# Sheet1.net
KiCad netlist of a schematic drawn in Altium Designer
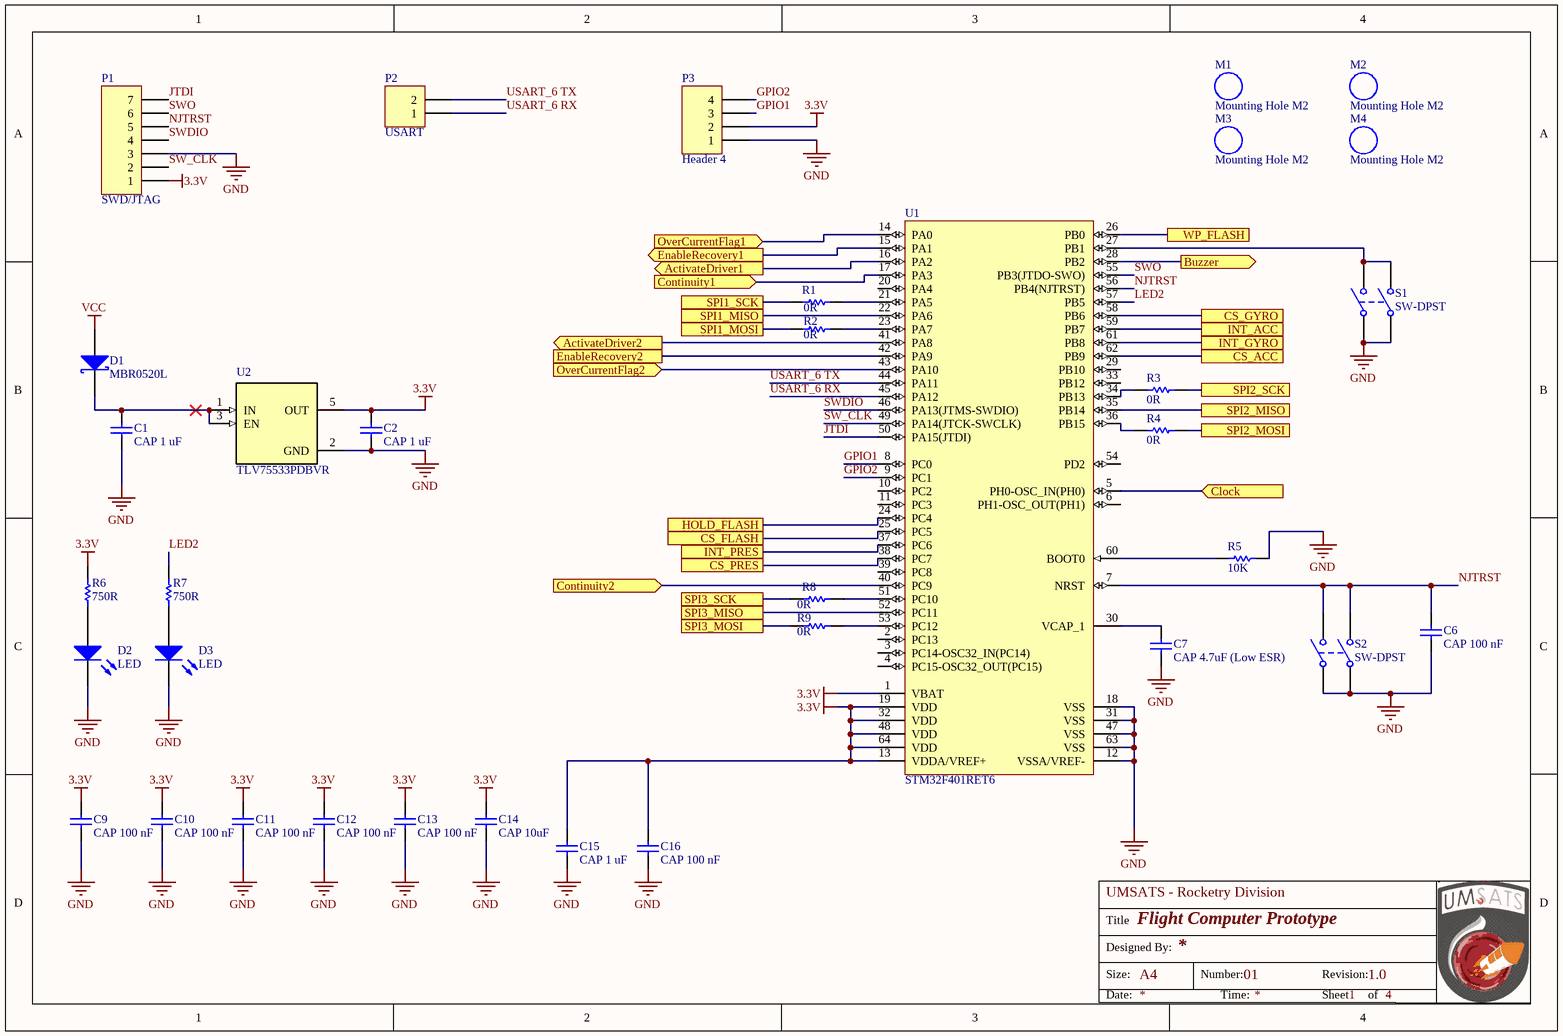
[diagram p0: Sheet1.SchDoc]

(export (version "E")
  (design (tool "Eeschema 10.0.6"))
  (components
    (comp (ref "C1")
      (value "CAP 1 uF")
      (footprint "CL10A105KB8NNNC")
      (description "Capacitor")
      (fields (field (name "PUBLISHER") "Altium Limited"))
      (libsource (lib "Miscellaneous Devices") (part "Cap"))
    )
    (comp (ref "C2")
      (value "CAP 1 uF")
      (footprint "CL10A105KB8NNNC")
      (description "Capacitor")
      (fields (field (name "PUBLISHER") "Altium Limited"))
      (libsource (lib "Miscellaneous Devices") (part "Cap"))
    )
    (comp (ref "C6")
      (value "CAP 100 nF")
      (footprint "06035C104KAT4A")
      (description "Capacitor")
      (fields (field (name "PUBLISHER") "Altium Limited"))
      (libsource (lib "Miscellaneous Devices") (part "Cap"))
    )
    (comp (ref "C7")
      (value "CAP 4.7uF (Low ESR)")
      (footprint "CGA5L1X7R1E475K160AC")
      (description "Capacitor")
      (fields (field (name "PUBLISHER") "Altium Limited"))
      (libsource (lib "Miscellaneous Devices") (part "Cap"))
    )
    (comp (ref "C9")
      (value "CAP 100 nF")
      (footprint "06035C104KAT4A")
      (description "Capacitor")
      (fields (field (name "PUBLISHER") "Altium Limited"))
      (libsource (lib "Miscellaneous Devices") (part "Cap"))
    )
    (comp (ref "C10")
      (value "CAP 100 nF")
      (footprint "06035C104KAT4A")
      (description "Capacitor")
      (fields (field (name "PUBLISHER") "Altium Limited"))
      (libsource (lib "Miscellaneous Devices") (part "Cap"))
    )
    (comp (ref "C11")
      (value "CAP 100 nF")
      (footprint "06035C104KAT4A")
      (description "Capacitor")
      (fields (field (name "PUBLISHER") "Altium Limited"))
      (libsource (lib "Miscellaneous Devices") (part "Cap"))
    )
    (comp (ref "C12")
      (value "CAP 100 nF")
      (footprint "06035C104KAT4A")
      (description "Capacitor")
      (fields (field (name "PUBLISHER") "Altium Limited"))
      (libsource (lib "Miscellaneous Devices") (part "Cap"))
    )
    (comp (ref "C13")
      (value "CAP 100 nF")
      (footprint "06035C104KAT4A")
      (description "Capacitor")
      (fields (field (name "PUBLISHER") "Altium Limited"))
      (libsource (lib "Miscellaneous Devices") (part "Cap"))
    )
    (comp (ref "C14")
      (value "CAP 10uF")
      (footprint "CL31A106KAHNFNE")
      (description "Capacitor")
      (fields (field (name "PUBLISHER") "Altium Limited"))
      (libsource (lib "Miscellaneous Devices") (part "Cap"))
    )
    (comp (ref "C15")
      (value "CAP 1 uF")
      (footprint "CL10A105KB8NNNC")
      (description "Capacitor")
      (fields (field (name "PUBLISHER") "Altium Limited"))
      (libsource (lib "Miscellaneous Devices") (part "Cap"))
    )
    (comp (ref "C16")
      (value "CAP 100 nF")
      (footprint "06035C104KAT4A")
      (description "Capacitor")
      (fields (field (name "PUBLISHER") "Altium Limited"))
      (libsource (lib "Miscellaneous Devices") (part "Cap"))
    )
    (comp (ref "D1")
      (value "MBR0520L")
      (footprint "ON_Semi_CASE_425_0")
      (description "Schottky Diode")
      (fields (field (name "MANUFACTURER") "ON Semiconductor / Fairchild"))
      (libsource (lib "MBR0520L") (part "MBR0520L"))
    )
    (comp (ref "D2")
      (value "LED")
      (footprint "Vishay VLMx20 Low Current Mini SMD LED")
      (description "Typical RED, GREEN, YELLOW, AMBER GaAs LED")
      (fields (field (name "PUBLISHER") "Altium Limited"))
      (libsource (lib "Miscellaneous Devices") (part "LED2"))
    )
    (comp (ref "D3")
      (value "LED")
      (footprint "Vishay VLMx20 Low Current Mini SMD LED")
      (description "Typical RED, GREEN, YELLOW, AMBER GaAs LED")
      (fields (field (name "PUBLISHER") "Altium Limited"))
      (libsource (lib "Miscellaneous Devices") (part "LED2"))
    )
    (comp (ref "M1")
      (value "Mounting Hole M2")
      (footprint "Mounting Hole M2")
      (libsource (lib "MountingHoleM2") (part "Mounting Hole M2"))
    )
    (comp (ref "M2")
      (value "Mounting Hole M2")
      (footprint "Mounting Hole M2")
      (libsource (lib "MountingHoleM2") (part "Mounting Hole M2"))
    )
    (comp (ref "M3")
      (value "Mounting Hole M2")
      (footprint "Mounting Hole M2")
      (libsource (lib "MountingHoleM2") (part "Mounting Hole M2"))
    )
    (comp (ref "M4")
      (value "Mounting Hole M2")
      (footprint "Mounting Hole M2")
      (libsource (lib "MountingHoleM2") (part "Mounting Hole M2"))
    )
    (comp (ref "P1")
      (value "SWD/JTAG")
      (footprint "HDR1X7")
      (description "Header, 7-Pin")
      (fields (field (name "PUBLISHER") "Altium Limited"))
      (libsource (lib "Miscellaneous Connectors") (part "Header 7"))
    )
    (comp (ref "P2")
      (value "USART")
      (footprint "HDR1X2")
      (description "Header, 2-Pin")
      (fields (field (name "PUBLISHER") "Altium Limited"))
      (libsource (lib "Miscellaneous Connectors") (part "Header 2"))
    )
    (comp (ref "P3")
      (value "Header 4")
      (footprint "HDR1X4")
      (description "Header, 4-Pin")
      (fields (field (name "PUBLISHER") "Altium Limited"))
      (libsource (lib "Miscellaneous Connectors") (part "Header 4"))
    )
    (comp (ref "R1")
      (value "0R")
      (footprint "CR0603-J/-000ELF")
      (description "Resistor")
      (fields (field (name "PUBLISHER") "Altium Limited"))
      (libsource (lib "Miscellaneous Devices") (part "Res1"))
    )
    (comp (ref "R2")
      (value "0R")
      (footprint "CR0603-J/-000ELF")
      (description "Resistor")
      (fields (field (name "PUBLISHER") "Altium Limited"))
      (libsource (lib "Miscellaneous Devices") (part "Res1"))
    )
    (comp (ref "R3")
      (value "0R")
      (footprint "CR0603-J/-000ELF")
      (description "Resistor")
      (fields (field (name "PUBLISHER") "Altium Limited"))
      (libsource (lib "Miscellaneous Devices") (part "Res1"))
    )
    (comp (ref "R4")
      (value "0R")
      (footprint "CR0603-J/-000ELF")
      (description "Resistor")
      (fields (field (name "PUBLISHER") "Altium Limited"))
      (libsource (lib "Miscellaneous Devices") (part "Res1"))
    )
    (comp (ref "R5")
      (value "10K")
      (footprint "RK73H1JTTD1002F")
      (description "Resistor")
      (fields (field (name "PUBLISHER") "Altium Limited"))
      (libsource (lib "Miscellaneous Devices") (part "Res1"))
    )
    (comp (ref "R6")
      (value "750R")
      (footprint "CRCW0603750RFKEA")
      (description "Resistor")
      (fields (field (name "PUBLISHER") "Altium Limited"))
      (libsource (lib "Miscellaneous Devices") (part "Res1"))
    )
    (comp (ref "R7")
      (value "750R")
      (footprint "CRCW0603750RFKEA")
      (description "Resistor")
      (fields (field (name "PUBLISHER") "Altium Limited"))
      (libsource (lib "Miscellaneous Devices") (part "Res1"))
    )
    (comp (ref "R8")
      (value "0R")
      (footprint "CR0603-J/-000ELF")
      (description "Resistor")
      (fields (field (name "PUBLISHER") "Altium Limited"))
      (libsource (lib "Miscellaneous Devices") (part "Res1"))
    )
    (comp (ref "R9")
      (value "0R")
      (footprint "CR0603-J/-000ELF")
      (description "Resistor")
      (fields (field (name "PUBLISHER") "Altium Limited"))
      (libsource (lib "Miscellaneous Devices") (part "Res1"))
    )
    (comp (ref "S1")
      (value "SW-DPST")
      (footprint "PTS530GG065SMTRLFS")
      (description "Double-Pole, Single-Throw Switch")
      (fields (field (name "PUBLISHER") "Altium Limited"))
      (libsource (lib "Miscellaneous Devices") (part "SW-DPST"))
    )
    (comp (ref "S2")
      (value "SW-DPST")
      (footprint "PTS530GG065SMTRLFS")
      (description "Double-Pole, Single-Throw Switch")
      (fields (field (name "PUBLISHER") "Altium Limited"))
      (libsource (lib "Miscellaneous Devices") (part "SW-DPST"))
    )
    (comp (ref "U1")
      (value "STM32F401RET6")
      (footprint "STM-LQFP64_N")
      (libsource (lib "STM32F401RET6") (part "STM32F401RET6"))
    )
    (comp (ref "U2")
      (value "TLV75533PDBVR")
      (footprint "SOT95P280X145-5N")
      (description "500mA Low-IQ Small-Size Low-Dropout _LDO_ Regulator 5-SOT-23 -40 to 125")
      (fields (field (name "MF") "Texas Instruments"))
      (libsource (lib "TLV75533PDBVR") (part "TLV75533PDBVR"))
    )
  )
  (nets
    (net (code "1") (name "/ActivateDriver1") (class "Default")
      (node (ref "U1") (pin "16") (pinfunction "PA2_16") (pintype "bidirectional"))
    )
    (net (code "2") (name "/ActivateDriver2") (class "Default")
      (node (ref "U1") (pin "41") (pinfunction "PA8_41") (pintype "bidirectional"))
    )
    (net (code "3") (name "/Buzzer") (class "Default")
      (node (ref "U1") (pin "28") (pinfunction "PB2_28") (pintype "bidirectional"))
    )
    (net (code "4") (name "/CS_ACC") (class "Default")
      (node (ref "U1") (pin "62") (pinfunction "PB9_62") (pintype "bidirectional"))
    )
    (net (code "5") (name "/CS_FLASH") (class "Default")
      (node (ref "U1") (pin "25") (pinfunction "PC5_25") (pintype "bidirectional"))
    )
    (net (code "6") (name "/CS_GYRO") (class "Default")
      (node (ref "U1") (pin "58") (pinfunction "PB6_58") (pintype "bidirectional"))
    )
    (net (code "7") (name "/CS_PRES") (class "Default")
      (node (ref "U1") (pin "38") (pinfunction "PC7_38") (pintype "bidirectional"))
    )
    (net (code "8") (name "/Clock") (class "Default")
      (node (ref "U1") (pin "5") (pinfunction "PH0-OSC_IN(PH0)_5") (pintype "bidirectional"))
    )
    (net (code "9") (name "/Continuity1") (class "Default")
      (node (ref "U1") (pin "17") (pinfunction "PA3_17") (pintype "bidirectional"))
    )
    (net (code "10") (name "/Continuity2") (class "Default")
      (node (ref "U1") (pin "40") (pinfunction "PC9_40") (pintype "bidirectional"))
    )
    (net (code "11") (name "/EnableRecovery1") (class "Default")
      (node (ref "U1") (pin "15") (pinfunction "PA1_15") (pintype "bidirectional"))
    )
    (net (code "12") (name "/EnableRecovery2") (class "Default")
      (node (ref "U1") (pin "42") (pinfunction "PA9_42") (pintype "bidirectional"))
    )
    (net (code "13") (name "/GPIO1") (class "Default")
      (node (ref "P3") (pin "3") (pinfunction "3_3") (pintype "passive"))
      (node (ref "U1") (pin "8") (pinfunction "PC0_8") (pintype "bidirectional"))
    )
    (net (code "14") (name "/GPIO2") (class "Default")
      (node (ref "P3") (pin "4") (pinfunction "4_4") (pintype "passive"))
      (node (ref "U1") (pin "9") (pinfunction "PC1_9") (pintype "bidirectional"))
    )
    (net (code "15") (name "/HOLD_FLASH") (class "Default")
      (node (ref "U1") (pin "24") (pinfunction "PC4_24") (pintype "bidirectional"))
    )
    (net (code "16") (name "/INT_ACC") (class "Default")
      (node (ref "U1") (pin "59") (pinfunction "PB7_59") (pintype "bidirectional"))
    )
    (net (code "17") (name "/INT_GYRO") (class "Default")
      (node (ref "U1") (pin "61") (pinfunction "PB8_61") (pintype "bidirectional"))
    )
    (net (code "18") (name "/INT_PRES") (class "Default")
      (node (ref "U1") (pin "37") (pinfunction "PC6_37") (pintype "bidirectional"))
    )
    (net (code "19") (name "/JTDI") (class "Default")
      (node (ref "P1") (pin "7") (pinfunction "7_7") (pintype "passive"))
      (node (ref "U1") (pin "50") (pinfunction "PA15(JTDI)_50") (pintype "bidirectional"))
    )
    (net (code "20") (name "/LED2") (class "Default")
      (node (ref "R7") (pin "2") (pinfunction "2_2") (pintype "passive"))
      (node (ref "U1") (pin "57") (pinfunction "PB5_57") (pintype "bidirectional"))
    )
    (net (code "21") (name "/NJTRST") (class "Default")
      (node (ref "C6") (pin "1") (pinfunction "1_1") (pintype "passive"))
      (node (ref "P1") (pin "5") (pinfunction "5_5") (pintype "passive"))
      (node (ref "S2") (pin "2") (pinfunction "NO1_2") (pintype "passive"))
      (node (ref "S2") (pin "4") (pinfunction "NO2_4") (pintype "passive"))
      (node (ref "U1") (pin "56") (pinfunction "PB4(NJTRST)_56") (pintype "bidirectional"))
      (node (ref "U1") (pin "7") (pinfunction "NRST_7") (pintype "bidirectional"))
    )
    (net (code "22") (name "/OverCurrentFlag1") (class "Default")
      (node (ref "U1") (pin "14") (pinfunction "PA0_14") (pintype "bidirectional"))
    )
    (net (code "23") (name "/OverCurrentFlag2") (class "Default")
      (node (ref "U1") (pin "43") (pinfunction "PA10_43") (pintype "bidirectional"))
    )
    (net (code "24") (name "/SPI1_MISO") (class "Default")
      (node (ref "U1") (pin "22") (pinfunction "PA6_22") (pintype "bidirectional"))
    )
    (net (code "25") (name "/SPI1_MOSI") (class "Default")
      (node (ref "R2") (pin "1") (pinfunction "1_1") (pintype "passive"))
    )
    (net (code "26") (name "/SPI1_SCK") (class "Default")
      (node (ref "R1") (pin "1") (pinfunction "1_1") (pintype "passive"))
    )
    (net (code "27") (name "/SPI2_MISO") (class "Default")
      (node (ref "U1") (pin "35") (pinfunction "PB14_35") (pintype "bidirectional"))
    )
    (net (code "28") (name "/SPI2_MOSI") (class "Default")
      (node (ref "R4") (pin "2") (pinfunction "2_2") (pintype "passive"))
    )
    (net (code "29") (name "/SPI2_SCK") (class "Default")
      (node (ref "R3") (pin "2") (pinfunction "2_2") (pintype "passive"))
    )
    (net (code "30") (name "/SPI3_MISO") (class "Default")
      (node (ref "U1") (pin "52") (pinfunction "PC11_52") (pintype "bidirectional"))
    )
    (net (code "31") (name "/SPI3_MOSI") (class "Default")
      (node (ref "R9") (pin "1") (pinfunction "1_1") (pintype "passive"))
    )
    (net (code "32") (name "/SPI3_SCK") (class "Default")
      (node (ref "R8") (pin "1") (pinfunction "1_1") (pintype "passive"))
    )
    (net (code "33") (name "/SWDIO") (class "Default")
      (node (ref "P1") (pin "4") (pinfunction "4_4") (pintype "passive"))
      (node (ref "U1") (pin "46") (pinfunction "PA13(JTMS-SWDIO)_46") (pintype "bidirectional"))
    )
    (net (code "34") (name "/SWO") (class "Default")
      (node (ref "P1") (pin "6") (pinfunction "6_6") (pintype "passive"))
      (node (ref "U1") (pin "55") (pinfunction "PB3(JTDO-SWO)_55") (pintype "bidirectional"))
    )
    (net (code "35") (name "/SW_CLK") (class "Default")
      (node (ref "P1") (pin "2") (pinfunction "2_2") (pintype "passive"))
      (node (ref "U1") (pin "49") (pinfunction "PA14(JTCK-SWCLK)_49") (pintype "bidirectional"))
    )
    (net (code "36") (name "/USART_6 RX") (class "Default")
      (node (ref "P2") (pin "1") (pinfunction "1_1") (pintype "passive"))
      (node (ref "U1") (pin "45") (pinfunction "PA12_45") (pintype "bidirectional"))
    )
    (net (code "37") (name "/USART_6 TX") (class "Default")
      (node (ref "P2") (pin "2") (pinfunction "2_2") (pintype "passive"))
      (node (ref "U1") (pin "44") (pinfunction "PA11_44") (pintype "bidirectional"))
    )
    (net (code "38") (name "/WP_FLASH") (class "Default")
      (node (ref "U1") (pin "26") (pinfunction "PB0_26") (pintype "bidirectional"))
    )
    (net (code "39") (name "3.3V") (class "Default")
      (node (ref "C10") (pin "1") (pinfunction "1_1") (pintype "passive"))
      (node (ref "C11") (pin "1") (pinfunction "1_1") (pintype "passive"))
      (node (ref "C12") (pin "1") (pinfunction "1_1") (pintype "passive"))
      (node (ref "C13") (pin "1") (pinfunction "1_1") (pintype "passive"))
      (node (ref "C14") (pin "2") (pinfunction "2_2") (pintype "passive"))
      (node (ref "C15") (pin "1") (pinfunction "1_1") (pintype "passive"))
      (node (ref "C16") (pin "1") (pinfunction "1_1") (pintype "passive"))
      (node (ref "C2") (pin "1") (pinfunction "1_1") (pintype "passive"))
      (node (ref "C9") (pin "1") (pinfunction "1_1") (pintype "passive"))
      (node (ref "P1") (pin "1") (pinfunction "1_1") (pintype "passive"))
      (node (ref "P3") (pin "2") (pinfunction "2_2") (pintype "passive"))
      (node (ref "R6") (pin "2") (pinfunction "2_2") (pintype "passive"))
      (node (ref "U1") (pin "1") (pinfunction "VBAT_1") (pintype "power_in"))
      (node (ref "U1") (pin "13") (pinfunction "VDDA/VREF+_13") (pintype "power_in"))
      (node (ref "U1") (pin "19") (pinfunction "VDD_19") (pintype "power_in"))
      (node (ref "U1") (pin "32") (pinfunction "VDD_32") (pintype "power_in"))
      (node (ref "U1") (pin "48") (pinfunction "VDD_48") (pintype "power_in"))
      (node (ref "U1") (pin "64") (pinfunction "VDD_64") (pintype "power_in"))
      (node (ref "U2") (pin "5") (pinfunction "OUT_5") (pintype "power_in"))
    )
    (net (code "40") (name "GND") (class "Default")
      (node (ref "C1") (pin "2") (pinfunction "2_2") (pintype "passive"))
      (node (ref "C10") (pin "2") (pinfunction "2_2") (pintype "passive"))
      (node (ref "C11") (pin "2") (pinfunction "2_2") (pintype "passive"))
      (node (ref "C12") (pin "2") (pinfunction "2_2") (pintype "passive"))
      (node (ref "C13") (pin "2") (pinfunction "2_2") (pintype "passive"))
      (node (ref "C14") (pin "1") (pinfunction "1_1") (pintype "passive"))
      (node (ref "C15") (pin "2") (pinfunction "2_2") (pintype "passive"))
      (node (ref "C16") (pin "2") (pinfunction "2_2") (pintype "passive"))
      (node (ref "C2") (pin "2") (pinfunction "2_2") (pintype "passive"))
      (node (ref "C6") (pin "2") (pinfunction "2_2") (pintype "passive"))
      (node (ref "C7") (pin "2") (pinfunction "2_2") (pintype "passive"))
      (node (ref "C9") (pin "2") (pinfunction "2_2") (pintype "passive"))
      (node (ref "D2") (pin "2") (pinfunction "K_2") (pintype "passive"))
      (node (ref "D3") (pin "2") (pinfunction "K_2") (pintype "passive"))
      (node (ref "P1") (pin "3") (pinfunction "3_3") (pintype "passive"))
      (node (ref "P3") (pin "1") (pinfunction "1_1") (pintype "passive"))
      (node (ref "R5") (pin "2") (pinfunction "2_2") (pintype "passive"))
      (node (ref "S1") (pin "1") (pinfunction "COMMON1_1") (pintype "passive"))
      (node (ref "S1") (pin "3") (pinfunction "COMMON2_3") (pintype "passive"))
      (node (ref "S2") (pin "1") (pinfunction "COMMON1_1") (pintype "passive"))
      (node (ref "S2") (pin "3") (pinfunction "COMMON2_3") (pintype "passive"))
      (node (ref "U1") (pin "12") (pinfunction "VSSA/VREF-_12") (pintype "power_in"))
      (node (ref "U1") (pin "18") (pinfunction "VSS_18") (pintype "power_in"))
      (node (ref "U1") (pin "31") (pinfunction "VSS_31") (pintype "power_in"))
      (node (ref "U1") (pin "47") (pinfunction "VSS_47") (pintype "power_in"))
      (node (ref "U1") (pin "63") (pinfunction "VSS_63") (pintype "power_in"))
      (node (ref "U2") (pin "2") (pinfunction "GND_2") (pintype "power_in"))
    )
    (net (code "41") (name "Net-(D1-K)") (class "Default")
      (node (ref "C1") (pin "1") (pinfunction "1_1") (pintype "passive"))
      (node (ref "D1") (pin "2") (pinfunction "K_2") (pintype "passive"))
      (node (ref "U2") (pin "1") (pinfunction "IN_1") (pintype "input"))
      (node (ref "U2") (pin "3") (pinfunction "EN_3") (pintype "input"))
    )
    (net (code "42") (name "Net-(D2-A)") (class "Default")
      (node (ref "D2") (pin "1") (pinfunction "A_1") (pintype "passive"))
      (node (ref "R6") (pin "1") (pinfunction "1_1") (pintype "passive"))
    )
    (net (code "43") (name "Net-(D3-A)") (class "Default")
      (node (ref "D3") (pin "1") (pinfunction "A_1") (pintype "passive"))
      (node (ref "R7") (pin "1") (pinfunction "1_1") (pintype "passive"))
    )
    (net (code "44") (name "Net-(S1-NO1)") (class "Default")
      (node (ref "S1") (pin "2") (pinfunction "NO1_2") (pintype "passive"))
      (node (ref "S1") (pin "4") (pinfunction "NO2_4") (pintype "passive"))
      (node (ref "U1") (pin "27") (pinfunction "PB1_27") (pintype "bidirectional"))
    )
    (net (code "45") (name "Net-(U1-BOOT0)") (class "Default")
      (node (ref "R5") (pin "1") (pinfunction "1_1") (pintype "passive"))
      (node (ref "U1") (pin "60") (pinfunction "BOOT0_60") (pintype "input"))
    )
    (net (code "46") (name "Net-(U1-PA5)") (class "Default")
      (node (ref "R1") (pin "2") (pinfunction "2_2") (pintype "passive"))
      (node (ref "U1") (pin "21") (pinfunction "PA5_21") (pintype "bidirectional"))
    )
    (net (code "47") (name "Net-(U1-PA7)") (class "Default")
      (node (ref "R2") (pin "2") (pinfunction "2_2") (pintype "passive"))
      (node (ref "U1") (pin "23") (pinfunction "PA7_23") (pintype "bidirectional"))
    )
    (net (code "48") (name "Net-(U1-PB13)") (class "Default")
      (node (ref "R3") (pin "1") (pinfunction "1_1") (pintype "passive"))
      (node (ref "U1") (pin "34") (pinfunction "PB13_34") (pintype "bidirectional"))
    )
    (net (code "49") (name "Net-(U1-PB15)") (class "Default")
      (node (ref "R4") (pin "1") (pinfunction "1_1") (pintype "passive"))
      (node (ref "U1") (pin "36") (pinfunction "PB15_36") (pintype "bidirectional"))
    )
    (net (code "50") (name "Net-(U1-PC10)") (class "Default")
      (node (ref "R8") (pin "2") (pinfunction "2_2") (pintype "passive"))
      (node (ref "U1") (pin "51") (pinfunction "PC10_51") (pintype "bidirectional"))
    )
    (net (code "51") (name "Net-(U1-PC12)") (class "Default")
      (node (ref "R9") (pin "2") (pinfunction "2_2") (pintype "passive"))
      (node (ref "U1") (pin "53") (pinfunction "PC12_53") (pintype "bidirectional"))
    )
    (net (code "52") (name "Net-(U1-VCAP_1)") (class "Default")
      (node (ref "C7") (pin "1") (pinfunction "1_1") (pintype "passive"))
      (node (ref "U1") (pin "30") (pinfunction "VCAP_1_30") (pintype "passive"))
    )
    (net (code "53") (name "VCC") (class "Default")
      (node (ref "D1") (pin "1") (pinfunction "A_1") (pintype "passive"))
    )
    (net (code "54") (name "unconnected-(U1-PA4-Pad20)") (class "Default")
      (node (ref "U1") (pin "20") (pinfunction "PA4_20") (pintype "bidirectional"))
    )
    (net (code "55") (name "unconnected-(U1-PB10-Pad29)") (class "Default")
      (node (ref "U1") (pin "29") (pinfunction "PB10_29") (pintype "bidirectional"))
    )
    (net (code "56") (name "unconnected-(U1-PB12-Pad33)") (class "Default")
      (node (ref "U1") (pin "33") (pinfunction "PB12_33") (pintype "bidirectional"))
    )
    (net (code "57") (name "unconnected-(U1-PC2-Pad10)") (class "Default")
      (node (ref "U1") (pin "10") (pinfunction "PC2_10") (pintype "bidirectional"))
    )
    (net (code "58") (name "unconnected-(U1-PC3-Pad11)") (class "Default")
      (node (ref "U1") (pin "11") (pinfunction "PC3_11") (pintype "bidirectional"))
    )
    (net (code "59") (name "unconnected-(U1-PC8-Pad39)") (class "Default")
      (node (ref "U1") (pin "39") (pinfunction "PC8_39") (pintype "bidirectional"))
    )
    (net (code "60") (name "unconnected-(U1-PC13-Pad2)") (class "Default")
      (node (ref "U1") (pin "2") (pinfunction "PC13_2") (pintype "bidirectional"))
    )
    (net (code "61") (name "unconnected-(U1-PC14-OSC32_IN(PC14)-Pad3)") (class "Default")
      (node (ref "U1") (pin "3") (pinfunction "PC14-OSC32_IN(PC14)_3") (pintype "bidirectional"))
    )
    (net (code "62") (name "unconnected-(U1-PC15-OSC32_OUT(PC15)-Pad4)") (class "Default")
      (node (ref "U1") (pin "4") (pinfunction "PC15-OSC32_OUT(PC15)_4") (pintype "bidirectional"))
    )
    (net (code "63") (name "unconnected-(U1-PD2-Pad54)") (class "Default")
      (node (ref "U1") (pin "54") (pinfunction "PD2_54") (pintype "bidirectional"))
    )
    (net (code "64") (name "unconnected-(U1-PH1-OSC_OUT(PH1)-Pad6)") (class "Default")
      (node (ref "U1") (pin "6") (pinfunction "PH1-OSC_OUT(PH1)_6") (pintype "bidirectional"))
    )
  )
)
